# breakout_MDBT40.net
KiCad netlist of a schematic drawn in EAGLE
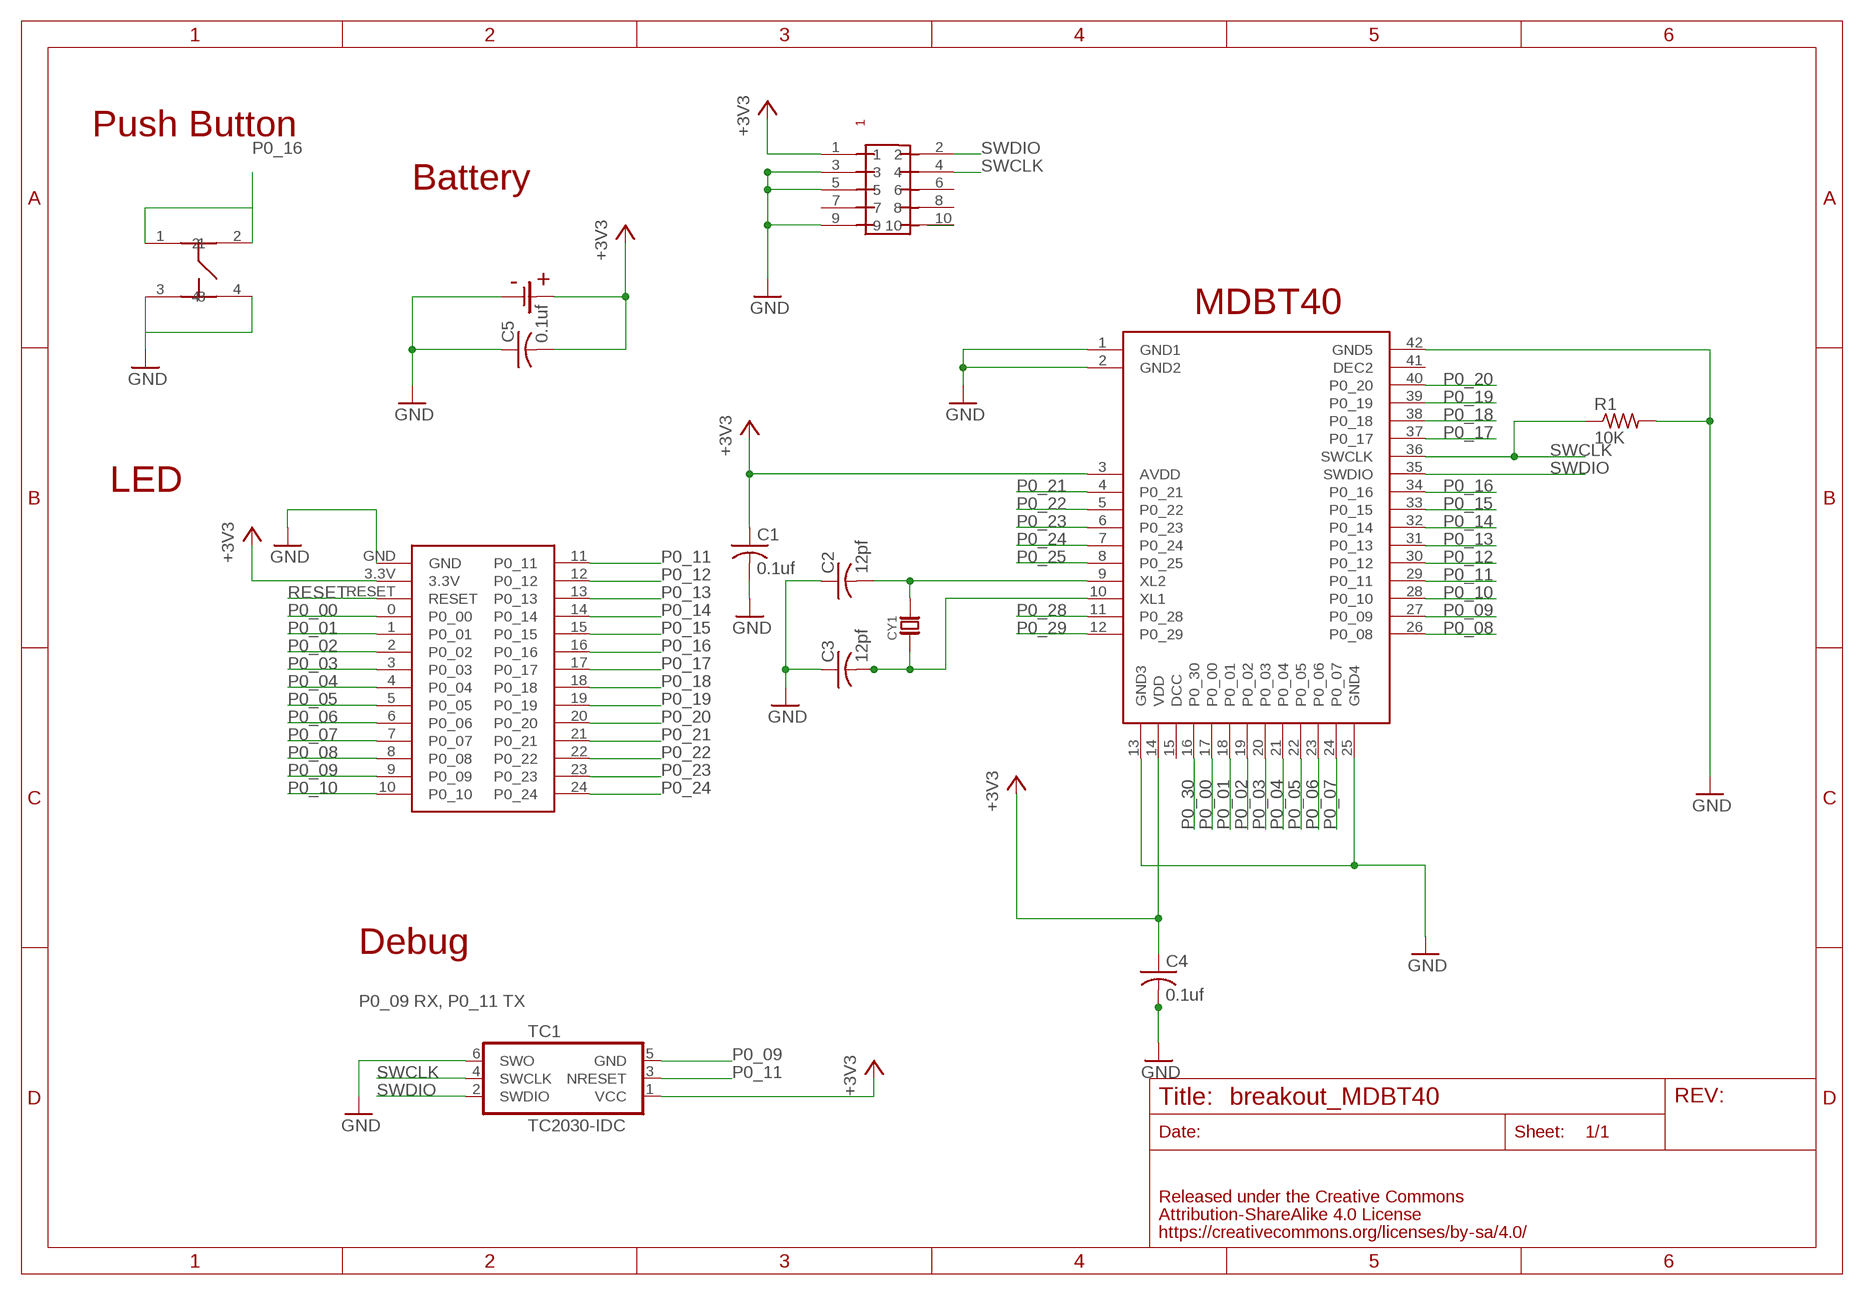
[diagram p0: schematic, sheet 1]

(export (version "E")
  (design (tool "Eeschema 10.0.6"))
  (components
    (comp (ref "C1")
      (value "0.1uf")
      (footprint "eagle-import:C0603")
      (libsource (lib "eagle-import") (part "C-USC0603"))
    )
    (comp (ref "C2")
      (value "12pf")
      (footprint "eagle-import:C0603")
      (libsource (lib "eagle-import") (part "C-USC0603"))
    )
    (comp (ref "C3")
      (value "12pf")
      (footprint "eagle-import:C0603")
      (libsource (lib "eagle-import") (part "C-USC0603"))
    )
    (comp (ref "C4")
      (value "0.1uf")
      (footprint "eagle-import:C0603")
      (libsource (lib "eagle-import") (part "C-USC0603"))
    )
    (comp (ref "C5")
      (value "0.1uf")
      (footprint "eagle-import:C0603")
      (libsource (lib "eagle-import") (part "C-USC0603"))
    )
    (comp (ref "CY1")
      (value "CRYSTALABS07")
      (footprint "eagle-import:ABRACOM-ABS07-32.768KHZ")
      (libsource (lib "eagle-import") (part "CRYSTALABS07"))
    )
    (comp (ref "R1")
      (value "10K")
      (footprint "eagle-import:R0603")
      (libsource (lib "eagle-import") (part "R-US_R0603"))
    )
    (comp (ref "TC1")
      (value "TC2030-IDC")
      (footprint "eagle-import:TC2030-IDC")
      (libsource (lib "eagle-import") (part "TC2030-IDC"))
    )
    (comp (ref "U$1")
      (value "RAYTAC-MDBT40")
      (footprint "eagle-import:RAYTAC-MDBT40")
      (libsource (lib "eagle-import") (part "RAYTAC-MDBT40"))
    )
    (comp (ref "U$3")
      (value "BLE-BREAKOUT-NORDIC")
      (footprint "eagle-import:BLE-BREAKOUT-NORDIC")
      (libsource (lib "eagle-import") (part "BLE-BREAKOUT-NORDIC"))
    )
    (comp (ref "U$4")
      (value "PIN-HEADER-SMT(1.27MM)2X5")
      (footprint "eagle-import:PIN-HEADER-SMT(1.27MM)2X5")
      (libsource (lib "eagle-import") (part "PIN-HEADER-SMT(1.27MM)2X5"))
    )
    (comp (ref "U$5")
      (value "SWICTH-4P(KMR2)")
      (footprint "eagle-import:SWITCH-4P(KMR2)")
      (libsource (lib "eagle-import") (part "SWICTH-4P(KMR2)"))
    )
    (comp (ref "U$8")
      (value "SMTU-TOP2032")
      (footprint "eagle-import:SMTU-2032")
      (libsource (lib "eagle-import") (part "SMTU-TOP2032"))
    )
  )
  (nets
    (net (code "1") (name "+3V3") (class "Default")
      (node (ref "C1") (pin "1") (pinfunction "1_1") (pintype "passive"))
      (node (ref "C4") (pin "1") (pinfunction "1_1") (pintype "passive"))
      (node (ref "C5") (pin "2") (pinfunction "2_2") (pintype "passive"))
      (node (ref "TC1") (pin "1") (pinfunction "VCC_1") (pintype "passive"))
      (node (ref "U$1") (pin "14") (pinfunction "VDD_14") (pintype "bidirectional"))
      (node (ref "U$1") (pin "3") (pinfunction "AVDD_3") (pintype "bidirectional"))
      (node (ref "U$3") (pin "3.3V") (pinfunction "3.3V_3.3V") (pintype "bidirectional"))
      (node (ref "U$4") (pin "1") (pinfunction "1_1") (pintype "bidirectional"))
      (node (ref "U$8") (pin "+") (pinfunction "+_+") (pintype "bidirectional"))
    )
    (net (code "2") (name "/P0_00") (class "Default")
      (node (ref "U$1") (pin "17") (pinfunction "P0_00_17") (pintype "bidirectional"))
      (node (ref "U$3") (pin "0") (pinfunction "P0_00_0") (pintype "bidirectional"))
    )
    (net (code "3") (name "/P0_01") (class "Default")
      (node (ref "U$1") (pin "18") (pinfunction "P0_01_18") (pintype "bidirectional"))
      (node (ref "U$3") (pin "1") (pinfunction "P0_01_1") (pintype "bidirectional"))
    )
    (net (code "4") (name "/P0_02") (class "Default")
      (node (ref "U$1") (pin "19") (pinfunction "P0_02_19") (pintype "bidirectional"))
      (node (ref "U$3") (pin "2") (pinfunction "P0_02_2") (pintype "bidirectional"))
    )
    (net (code "5") (name "/P0_03") (class "Default")
      (node (ref "U$1") (pin "20") (pinfunction "P0_03_20") (pintype "bidirectional"))
      (node (ref "U$3") (pin "3") (pinfunction "P0_03_3") (pintype "bidirectional"))
    )
    (net (code "6") (name "/P0_04") (class "Default")
      (node (ref "U$1") (pin "21") (pinfunction "P0_04_21") (pintype "bidirectional"))
      (node (ref "U$3") (pin "4") (pinfunction "P0_04_4") (pintype "bidirectional"))
    )
    (net (code "7") (name "/P0_05") (class "Default")
      (node (ref "U$1") (pin "22") (pinfunction "P0_05_22") (pintype "bidirectional"))
      (node (ref "U$3") (pin "5") (pinfunction "P0_05_5") (pintype "bidirectional"))
    )
    (net (code "8") (name "/P0_06") (class "Default")
      (node (ref "U$1") (pin "23") (pinfunction "P0_06_23") (pintype "bidirectional"))
      (node (ref "U$3") (pin "6") (pinfunction "P0_06_6") (pintype "bidirectional"))
    )
    (net (code "9") (name "/P0_07") (class "Default")
      (node (ref "U$1") (pin "24") (pinfunction "P0_07_24") (pintype "bidirectional"))
      (node (ref "U$3") (pin "7") (pinfunction "P0_07_7") (pintype "bidirectional"))
    )
    (net (code "10") (name "/P0_08") (class "Default")
      (node (ref "U$1") (pin "26") (pinfunction "P0_08_26") (pintype "bidirectional"))
      (node (ref "U$3") (pin "8") (pinfunction "P0_08_8") (pintype "bidirectional"))
    )
    (net (code "11") (name "/P0_09") (class "Default")
      (node (ref "TC1") (pin "5") (pinfunction "GND_5") (pintype "passive"))
      (node (ref "U$1") (pin "27") (pinfunction "P0_09_27") (pintype "bidirectional"))
      (node (ref "U$3") (pin "9") (pinfunction "P0_09_9") (pintype "bidirectional"))
    )
    (net (code "12") (name "/P0_10") (class "Default")
      (node (ref "U$1") (pin "28") (pinfunction "P0_10_28") (pintype "bidirectional"))
      (node (ref "U$3") (pin "10") (pinfunction "P0_10_10") (pintype "bidirectional"))
    )
    (net (code "13") (name "/P0_11") (class "Default")
      (node (ref "TC1") (pin "3") (pinfunction "NRESET_3") (pintype "passive"))
      (node (ref "U$1") (pin "29") (pinfunction "P0_11_29") (pintype "bidirectional"))
      (node (ref "U$3") (pin "11") (pinfunction "P0_11_11") (pintype "bidirectional"))
    )
    (net (code "14") (name "/P0_12") (class "Default")
      (node (ref "U$1") (pin "30") (pinfunction "P0_12_30") (pintype "bidirectional"))
      (node (ref "U$3") (pin "12") (pinfunction "P0_12_12") (pintype "bidirectional"))
    )
    (net (code "15") (name "/P0_13") (class "Default")
      (node (ref "U$1") (pin "31") (pinfunction "P0_13_31") (pintype "bidirectional"))
      (node (ref "U$3") (pin "13") (pinfunction "P0_13_13") (pintype "bidirectional"))
    )
    (net (code "16") (name "/P0_14") (class "Default")
      (node (ref "U$1") (pin "32") (pinfunction "P0_14_32") (pintype "bidirectional"))
      (node (ref "U$3") (pin "14") (pinfunction "P0_14_14") (pintype "bidirectional"))
    )
    (net (code "17") (name "/P0_15") (class "Default")
      (node (ref "U$1") (pin "33") (pinfunction "P0_15_33") (pintype "bidirectional"))
      (node (ref "U$3") (pin "15") (pinfunction "P0_15_15") (pintype "bidirectional"))
    )
    (net (code "18") (name "/P0_16") (class "Default")
      (node (ref "U$1") (pin "34") (pinfunction "P0_16_34") (pintype "bidirectional"))
      (node (ref "U$3") (pin "16") (pinfunction "P0_16_16") (pintype "bidirectional"))
      (node (ref "U$5") (pin "1") (pinfunction "1_1") (pintype "bidirectional"))
      (node (ref "U$5") (pin "2") (pinfunction "2_2") (pintype "bidirectional"))
    )
    (net (code "19") (name "/P0_17") (class "Default")
      (node (ref "U$1") (pin "37") (pinfunction "P0_17_37") (pintype "bidirectional"))
      (node (ref "U$3") (pin "17") (pinfunction "P0_17_17") (pintype "bidirectional"))
    )
    (net (code "20") (name "/P0_18") (class "Default")
      (node (ref "U$1") (pin "38") (pinfunction "P0_18_38") (pintype "bidirectional"))
      (node (ref "U$3") (pin "18") (pinfunction "P0_18_18") (pintype "bidirectional"))
    )
    (net (code "21") (name "/P0_19") (class "Default")
      (node (ref "U$1") (pin "39") (pinfunction "P0_19_39") (pintype "bidirectional"))
      (node (ref "U$3") (pin "19") (pinfunction "P0_19_19") (pintype "bidirectional"))
    )
    (net (code "22") (name "/P0_20") (class "Default")
      (node (ref "U$1") (pin "40") (pinfunction "P0_20_40") (pintype "bidirectional"))
      (node (ref "U$3") (pin "20") (pinfunction "P0_20_20") (pintype "bidirectional"))
    )
    (net (code "23") (name "/P0_21") (class "Default")
      (node (ref "U$1") (pin "4") (pinfunction "P0_21_4") (pintype "bidirectional"))
      (node (ref "U$3") (pin "21") (pinfunction "P0_21_21") (pintype "bidirectional"))
    )
    (net (code "24") (name "/P0_22") (class "Default")
      (node (ref "U$1") (pin "5") (pinfunction "P0_22_5") (pintype "bidirectional"))
      (node (ref "U$3") (pin "22") (pinfunction "P0_22_22") (pintype "bidirectional"))
    )
    (net (code "25") (name "/P0_23") (class "Default")
      (node (ref "U$1") (pin "6") (pinfunction "P0_23_6") (pintype "bidirectional"))
      (node (ref "U$3") (pin "23") (pinfunction "P0_23_23") (pintype "bidirectional"))
    )
    (net (code "26") (name "/P0_24") (class "Default")
      (node (ref "U$1") (pin "7") (pinfunction "P0_24_7") (pintype "bidirectional"))
      (node (ref "U$3") (pin "24") (pinfunction "P0_24_24") (pintype "bidirectional"))
    )
    (net (code "27") (name "/P0_25") (class "Default")
      (node (ref "U$1") (pin "8") (pinfunction "P0_25_8") (pintype "bidirectional"))
    )
    (net (code "28") (name "/P0_28") (class "Default")
      (node (ref "U$1") (pin "11") (pinfunction "P0_28_11") (pintype "bidirectional"))
    )
    (net (code "29") (name "/P0_29") (class "Default")
      (node (ref "U$1") (pin "12") (pinfunction "P0_29_12") (pintype "bidirectional"))
    )
    (net (code "30") (name "/P0_30") (class "Default")
      (node (ref "U$1") (pin "16") (pinfunction "P0_30_16") (pintype "bidirectional"))
    )
    (net (code "31") (name "/RESET") (class "Default")
      (node (ref "U$3") (pin "RESET") (pinfunction "RESET_RESET") (pintype "bidirectional"))
    )
    (net (code "32") (name "/SWCLK") (class "Default")
      (node (ref "R1") (pin "1") (pinfunction "1_1") (pintype "passive"))
      (node (ref "TC1") (pin "4") (pinfunction "SWCLK_4") (pintype "passive"))
      (node (ref "U$1") (pin "36") (pinfunction "SWCLK_36") (pintype "bidirectional"))
      (node (ref "U$4") (pin "4") (pinfunction "4_4") (pintype "bidirectional"))
    )
    (net (code "33") (name "/SWDIO") (class "Default")
      (node (ref "TC1") (pin "2") (pinfunction "SWDIO_2") (pintype "passive"))
      (node (ref "U$1") (pin "35") (pinfunction "SWDIO_35") (pintype "bidirectional"))
      (node (ref "U$4") (pin "2") (pinfunction "2_2") (pintype "bidirectional"))
    )
    (net (code "34") (name "GND") (class "Default")
      (node (ref "C1") (pin "2") (pinfunction "2_2") (pintype "passive"))
      (node (ref "C2") (pin "1") (pinfunction "1_1") (pintype "passive"))
      (node (ref "C3") (pin "1") (pinfunction "1_1") (pintype "passive"))
      (node (ref "C4") (pin "2") (pinfunction "2_2") (pintype "passive"))
      (node (ref "C5") (pin "1") (pinfunction "1_1") (pintype "passive"))
      (node (ref "R1") (pin "2") (pinfunction "2_2") (pintype "passive"))
      (node (ref "TC1") (pin "6") (pinfunction "SWO_6") (pintype "passive"))
      (node (ref "U$1") (pin "1") (pinfunction "GND1_1") (pintype "bidirectional"))
      (node (ref "U$1") (pin "13") (pinfunction "GND3_13") (pintype "bidirectional"))
      (node (ref "U$1") (pin "2") (pinfunction "GND2_2") (pintype "bidirectional"))
      (node (ref "U$1") (pin "25") (pinfunction "GND4_25") (pintype "bidirectional"))
      (node (ref "U$1") (pin "42") (pinfunction "GND5_42") (pintype "bidirectional"))
      (node (ref "U$3") (pin "GND") (pinfunction "GND_GND") (pintype "bidirectional"))
      (node (ref "U$4") (pin "3") (pinfunction "3_3") (pintype "bidirectional"))
      (node (ref "U$4") (pin "5") (pinfunction "5_5") (pintype "bidirectional"))
      (node (ref "U$4") (pin "9") (pinfunction "9_9") (pintype "bidirectional"))
      (node (ref "U$5") (pin "3") (pinfunction "3_3") (pintype "bidirectional"))
      (node (ref "U$5") (pin "4") (pinfunction "4_4") (pintype "bidirectional"))
      (node (ref "U$8") (pin "-") (pinfunction "-_-") (pintype "bidirectional"))
    )
    (net (code "35") (name "Net-(U$1-XL1)") (class "Default")
      (node (ref "C3") (pin "2") (pinfunction "2_2") (pintype "passive"))
      (node (ref "CY1") (pin "P$1") (pinfunction "P$1_P$1") (pintype "bidirectional"))
      (node (ref "U$1") (pin "10") (pinfunction "XL1_10") (pintype "bidirectional"))
    )
    (net (code "36") (name "Net-(U$1-XL2)") (class "Default")
      (node (ref "C2") (pin "2") (pinfunction "2_2") (pintype "passive"))
      (node (ref "CY1") (pin "P$2") (pinfunction "P$2_P$2") (pintype "bidirectional"))
      (node (ref "U$1") (pin "9") (pinfunction "XL2_9") (pintype "bidirectional"))
    )
    (net (code "37") (name "unconnected-(U$1-DCC-Pad15)") (class "Default")
      (node (ref "U$1") (pin "15") (pinfunction "DCC_15") (pintype "bidirectional"))
    )
    (net (code "38") (name "unconnected-(U$1-DEC2-Pad41)") (class "Default")
      (node (ref "U$1") (pin "41") (pinfunction "DEC2_41") (pintype "bidirectional"))
    )
    (net (code "39") (name "unconnected-(U$4-Pad6)") (class "Default")
      (node (ref "U$4") (pin "6") (pinfunction "6_6") (pintype "bidirectional"))
    )
    (net (code "40") (name "unconnected-(U$4-Pad7)") (class "Default")
      (node (ref "U$4") (pin "7") (pinfunction "7_7") (pintype "bidirectional"))
    )
    (net (code "41") (name "unconnected-(U$4-Pad8)") (class "Default")
      (node (ref "U$4") (pin "8") (pinfunction "8_8") (pintype "bidirectional"))
    )
    (net (code "42") (name "unconnected-(U$4-Pad10)") (class "Default")
      (node (ref "U$4") (pin "10") (pinfunction "10_10") (pintype "bidirectional"))
    )
  )
)
